# FilamentBox.net
KiCad netlist of a schematic drawn in EAGLE
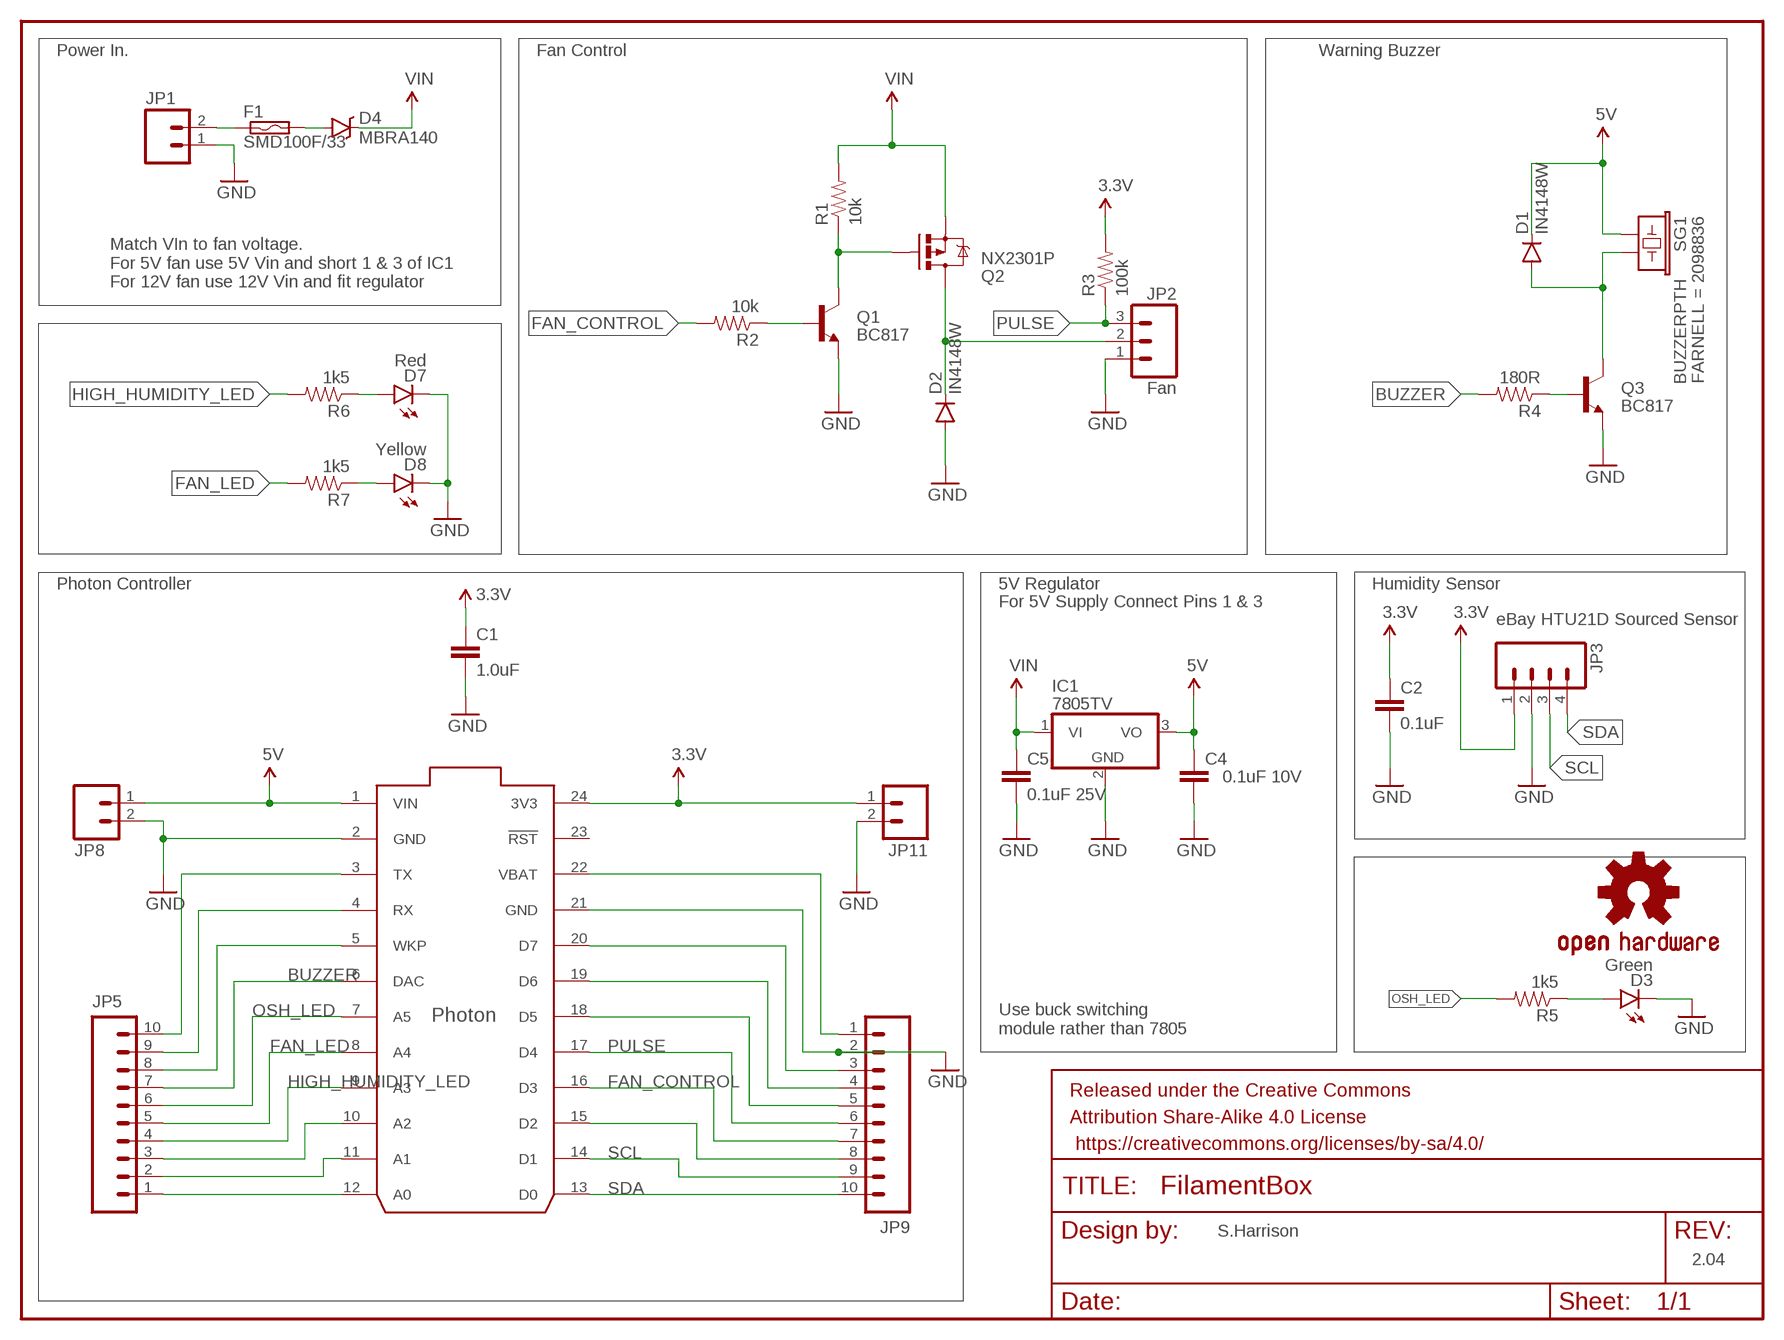
[diagram p0: schematic, sheet 1]

(export (version "E")
  (design (tool "Eeschema 10.0.6"))
  (components
    (comp (ref "C1")
      (value "1.0uF")
      (footprint "eagle-import:0805-CAP")
      (libsource (lib "eagle-import") (part "1.0UF-25V-+80/-20(0805){dblquote}"))
    )
    (comp (ref "C2")
      (value "0.1uF")
      (footprint "eagle-import:0805-CAP")
      (libsource (lib "eagle-import") (part "1.0UF-25V-+80/-20(0805){dblquote}"))
    )
    (comp (ref "C4")
      (value "0.1uF 10V")
      (footprint "eagle-import:0805-CAP")
      (libsource (lib "eagle-import") (part "1UF-25V-10%(0805){dblquote}"))
    )
    (comp (ref "C5")
      (value "0.1uF 25V")
      (footprint "eagle-import:0805-CAP")
      (libsource (lib "eagle-import") (part "1UF-25V-10%(0805){dblquote}"))
    )
    (comp (ref "D1")
      (value "IN4148W")
      (footprint "eagle-import:SOD-123")
      (libsource (lib "eagle-import") (part "DIODESOD123"))
    )
    (comp (ref "D2")
      (value "IN4148W")
      (footprint "eagle-import:SOD-123")
      (libsource (lib "eagle-import") (part "DIODESOD123"))
    )
    (comp (ref "D3")
      (value "Green")
      (footprint "eagle-import:LED-1206-BOTTOM")
      (libsource (lib "eagle-import") (part "LED1206-BOTTOM"))
    )
    (comp (ref "D4")
      (value "MBRA140")
      (footprint "eagle-import:SMA-DIODE")
      (libsource (lib "eagle-import") (part "DIODE-SCHOTTKY-MBRA140"))
    )
    (comp (ref "D7")
      (value "Red")
      (footprint "eagle-import:LED-1206-BOTTOM")
      (libsource (lib "eagle-import") (part "LED1206-BOTTOM"))
    )
    (comp (ref "D8")
      (value "Yellow")
      (footprint "eagle-import:LED-1206-BOTTOM")
      (libsource (lib "eagle-import") (part "LED1206-BOTTOM"))
    )
    (comp (ref "F1")
      (value "SMD100F/33")
      (footprint "eagle-import:SMD050F")
      (fields (field (name "MFG") "LITTLEFUSE") (field (name "MFGPART") "2920L075DR"))
      (libsource (lib "eagle-import") (part "SMDF/33100"))
    )
    (comp (ref "FRAME1")
      (value "FRAME-LETTER")
      (footprint "eagle-import:CREATIVE_COMMONS")
      (libsource (lib "eagle-import") (part "FRAME-LETTER"))
    )
    (comp (ref "IC1")
      (value "7805TV")
      (footprint "eagle-import:TO220V")
      (libsource (lib "eagle-import") (part "78TV05"))
    )
    (comp (ref "JP1")
      (value "M02POLAR")
      (footprint "eagle-import:MOLEX-1X2")
      (libsource (lib "eagle-import") (part "M02POLAR"))
    )
    (comp (ref "JP2")
      (value "Fan")
      (footprint "eagle-import:MOLEX-1X3")
      (libsource (lib "eagle-import") (part "M03POLAR"))
    )
    (comp (ref "JP3")
      (value "M04PTH")
      (footprint "eagle-import:1X04")
      (libsource (lib "eagle-import") (part "M04PTH"))
    )
    (comp (ref "JP5")
      (value "M10NO_SILK_PTH_FEMALE")
      (footprint "eagle-import:1X10_NO_SILK")
      (libsource (lib "eagle-import") (part "M10NO_SILK_PTH_FEMALE"))
    )
    (comp (ref "JP8")
      (value "M021X02_NO_SILK")
      (footprint "eagle-import:1X02_NO_SILK")
      (libsource (lib "eagle-import") (part "M021X02_NO_SILK"))
    )
    (comp (ref "JP9")
      (value "M10NO_SILK_PTH_FEMALE")
      (footprint "eagle-import:1X10_NO_SILK")
      (libsource (lib "eagle-import") (part "M10NO_SILK_PTH_FEMALE"))
    )
    (comp (ref "JP11")
      (value "M021X02_NO_SILK")
      (footprint "eagle-import:1X02_NO_SILK")
      (libsource (lib "eagle-import") (part "M021X02_NO_SILK"))
    )
    (comp (ref "LOGO1")
      (value "OSHW-LOGOL")
      (footprint "eagle-import:OSHW-LOGO-L")
      (libsource (lib "eagle-import") (part "OSHW-LOGOL"))
    )
    (comp (ref "Q1")
      (value "BC817")
      (footprint "eagle-import:SOT23-BEC")
      (libsource (lib "eagle-import") (part "BC817SMD-40"))
    )
    (comp (ref "Q2")
      (value "NX2301P")
      (footprint "eagle-import:SOT23-3")
      (libsource (lib "eagle-import") (part "MOSFET-PCHANNEL"))
    )
    (comp (ref "Q3")
      (value "BC817")
      (footprint "eagle-import:SOT23-BEC")
      (libsource (lib "eagle-import") (part "BC817SMD-40"))
    )
    (comp (ref "R1")
      (value "10k")
      (footprint "eagle-import:0805")
      (libsource (lib "eagle-import") (part "RESISTOR0805-RES"))
    )
    (comp (ref "R2")
      (value "10k")
      (footprint "eagle-import:0805")
      (libsource (lib "eagle-import") (part "RESISTOR0805-RES"))
    )
    (comp (ref "R3")
      (value "100k")
      (footprint "eagle-import:0805")
      (libsource (lib "eagle-import") (part "RESISTOR0805-RES"))
    )
    (comp (ref "R4")
      (value "180R")
      (footprint "eagle-import:0805")
      (libsource (lib "eagle-import") (part "RESISTOR0805-RES"))
    )
    (comp (ref "R5")
      (value "1k5")
      (footprint "eagle-import:0805")
      (libsource (lib "eagle-import") (part "RESISTOR0805-RES"))
    )
    (comp (ref "R6")
      (value "1k5")
      (footprint "eagle-import:0805")
      (libsource (lib "eagle-import") (part "RESISTOR0805-RES"))
    )
    (comp (ref "R7")
      (value "1k5")
      (footprint "eagle-import:0805")
      (libsource (lib "eagle-import") (part "RESISTOR0805-RES"))
    )
    (comp (ref "SG1")
      (value "BUZZERPTH")
      (footprint "eagle-import:BUZZER-12MM")
      (fields (field (name "FARNELL") "2098836"))
      (libsource (lib "eagle-import") (part "BUZZERPTH"))
    )
    (comp (ref "U3")
      (value "PHOTON")
      (footprint "eagle-import:PHOTON")
      (libsource (lib "eagle-import") (part "PHOTON_WITH_HEADERS"))
    )
  )
  (nets
    (net (code "1") (name "3.3V") (class "Default")
      (node (ref "C1") (pin "1") (pinfunction "1_1") (pintype "passive"))
      (node (ref "C2") (pin "1") (pinfunction "1_1") (pintype "passive"))
      (node (ref "JP11") (pin "1") (pinfunction "1_1") (pintype "passive"))
      (node (ref "JP3") (pin "1") (pinfunction "1_1") (pintype "passive"))
      (node (ref "R3") (pin "2") (pinfunction "2_2") (pintype "passive"))
      (node (ref "U3") (pin "24") (pinfunction "3V3_24") (pintype "power_in"))
    )
    (net (code "2") (name "5V") (class "Default")
      (node (ref "C4") (pin "1") (pinfunction "1_1") (pintype "passive"))
      (node (ref "D1") (pin "C") (pinfunction "C_C") (pintype "passive"))
      (node (ref "IC1") (pin "3") (pinfunction "VO_3") (pintype "passive"))
      (node (ref "JP8") (pin "1") (pinfunction "1_1") (pintype "passive"))
      (node (ref "SG1") (pin "+") (pinfunction "1_+") (pintype "passive"))
      (node (ref "U3") (pin "1") (pinfunction "VIN_1") (pintype "power_in"))
    )
    (net (code "3") (name "BUZZER") (class "Default")
      (node (ref "JP5") (pin "7") (pinfunction "7_7") (pintype "passive"))
      (node (ref "R4") (pin "2") (pinfunction "2_2") (pintype "passive"))
      (node (ref "U3") (pin "6") (pinfunction "DAC_6") (pintype "bidirectional"))
    )
    (net (code "4") (name "FAN_CONTROL") (class "Default")
      (node (ref "JP9") (pin "7") (pinfunction "7_7") (pintype "passive"))
      (node (ref "R2") (pin "2") (pinfunction "2_2") (pintype "passive"))
      (node (ref "U3") (pin "16") (pinfunction "D3_16") (pintype "bidirectional"))
    )
    (net (code "5") (name "FAN_LED") (class "Default")
      (node (ref "JP5") (pin "5") (pinfunction "5_5") (pintype "passive"))
      (node (ref "R7") (pin "2") (pinfunction "2_2") (pintype "passive"))
      (node (ref "U3") (pin "8") (pinfunction "A4_8") (pintype "bidirectional"))
    )
    (net (code "6") (name "GND") (class "Default")
      (node (ref "C1") (pin "2") (pinfunction "2_2") (pintype "passive"))
      (node (ref "C2") (pin "2") (pinfunction "2_2") (pintype "passive"))
      (node (ref "C4") (pin "2") (pinfunction "2_2") (pintype "passive"))
      (node (ref "C5") (pin "2") (pinfunction "2_2") (pintype "passive"))
      (node (ref "D2") (pin "A") (pinfunction "A_A") (pintype "passive"))
      (node (ref "D3") (pin "C") (pinfunction "C_C") (pintype "passive"))
      (node (ref "D7") (pin "C") (pinfunction "C_C") (pintype "passive"))
      (node (ref "D8") (pin "C") (pinfunction "C_C") (pintype "passive"))
      (node (ref "IC1") (pin "2") (pinfunction "GND_2") (pintype "passive"))
      (node (ref "JP1") (pin "1") (pinfunction "1_1") (pintype "passive"))
      (node (ref "JP11") (pin "2") (pinfunction "2_2") (pintype "passive"))
      (node (ref "JP2") (pin "1") (pinfunction "1_1") (pintype "passive"))
      (node (ref "JP3") (pin "2") (pinfunction "2_2") (pintype "passive"))
      (node (ref "JP8") (pin "2") (pinfunction "2_2") (pintype "passive"))
      (node (ref "JP9") (pin "2") (pinfunction "2_2") (pintype "passive"))
      (node (ref "Q1") (pin "E") (pinfunction "E_E") (pintype "passive"))
      (node (ref "Q3") (pin "E") (pinfunction "E_E") (pintype "passive"))
      (node (ref "U3") (pin "2") (pinfunction "GND_2") (pintype "power_in"))
      (node (ref "U3") (pin "21") (pinfunction "GND_21") (pintype "power_in"))
    )
    (net (code "7") (name "HIGH_HUMIDITY_LED") (class "Default")
      (node (ref "JP5") (pin "4") (pinfunction "4_4") (pintype "passive"))
      (node (ref "R6") (pin "2") (pinfunction "2_2") (pintype "passive"))
      (node (ref "U3") (pin "9") (pinfunction "A3_9") (pintype "bidirectional"))
    )
    (net (code "8") (name "Net-(D3-PadA)") (class "Default")
      (node (ref "D3") (pin "A") (pinfunction "A_A") (pintype "passive"))
      (node (ref "R5") (pin "1") (pinfunction "1_1") (pintype "passive"))
    )
    (net (code "9") (name "Net-(D4-PadA)") (class "Default")
      (node (ref "D4") (pin "A") (pinfunction "A_A") (pintype "passive"))
      (node (ref "F1") (pin "2") (pinfunction "2_2") (pintype "passive"))
    )
    (net (code "10") (name "Net-(D7-PadA)") (class "Default")
      (node (ref "D7") (pin "A") (pinfunction "A_A") (pintype "passive"))
      (node (ref "R6") (pin "1") (pinfunction "1_1") (pintype "passive"))
    )
    (net (code "11") (name "Net-(D8-PadA)") (class "Default")
      (node (ref "D8") (pin "A") (pinfunction "A_A") (pintype "passive"))
      (node (ref "R7") (pin "1") (pinfunction "1_1") (pintype "passive"))
    )
    (net (code "12") (name "Net-(F1-Pad1)") (class "Default")
      (node (ref "F1") (pin "1") (pinfunction "1_1") (pintype "passive"))
      (node (ref "JP1") (pin "2") (pinfunction "2_2") (pintype "passive"))
    )
    (net (code "13") (name "Net-(Q1-PadB)") (class "Default")
      (node (ref "Q1") (pin "B") (pinfunction "B_B") (pintype "passive"))
      (node (ref "R2") (pin "1") (pinfunction "1_1") (pintype "passive"))
    )
    (net (code "14") (name "Net-(Q2-D)") (class "Default")
      (node (ref "D2") (pin "C") (pinfunction "C_C") (pintype "passive"))
      (node (ref "JP2") (pin "2") (pinfunction "2_2") (pintype "passive"))
      (node (ref "Q2") (pin "3") (pinfunction "D_3") (pintype "passive"))
    )
    (net (code "15") (name "Net-(Q2-G)") (class "Default")
      (node (ref "Q1") (pin "C") (pinfunction "C_C") (pintype "passive"))
      (node (ref "Q2") (pin "1") (pinfunction "G_1") (pintype "passive"))
      (node (ref "R1") (pin "1") (pinfunction "1_1") (pintype "passive"))
    )
    (net (code "16") (name "Net-(Q3-PadB)") (class "Default")
      (node (ref "Q3") (pin "B") (pinfunction "B_B") (pintype "passive"))
      (node (ref "R4") (pin "1") (pinfunction "1_1") (pintype "passive"))
    )
    (net (code "17") (name "Net-(SG1-2)") (class "Default")
      (node (ref "D1") (pin "A") (pinfunction "A_A") (pintype "passive"))
      (node (ref "Q3") (pin "C") (pinfunction "C_C") (pintype "passive"))
      (node (ref "SG1") (pin "-") (pinfunction "2_-") (pintype "passive"))
    )
    (net (code "18") (name "Net-(U3-A0)") (class "Default")
      (node (ref "JP5") (pin "1") (pinfunction "1_1") (pintype "passive"))
      (node (ref "U3") (pin "12") (pinfunction "A0_12") (pintype "bidirectional"))
    )
    (net (code "19") (name "Net-(U3-A1)") (class "Default")
      (node (ref "JP5") (pin "2") (pinfunction "2_2") (pintype "passive"))
      (node (ref "U3") (pin "11") (pinfunction "A1_11") (pintype "bidirectional"))
    )
    (net (code "20") (name "Net-(U3-A2)") (class "Default")
      (node (ref "JP5") (pin "3") (pinfunction "3_3") (pintype "passive"))
      (node (ref "U3") (pin "10") (pinfunction "A2_10") (pintype "bidirectional"))
    )
    (net (code "21") (name "Net-(U3-D2)") (class "Default")
      (node (ref "JP9") (pin "8") (pinfunction "8_8") (pintype "passive"))
      (node (ref "U3") (pin "15") (pinfunction "D2_15") (pintype "bidirectional"))
    )
    (net (code "22") (name "Net-(U3-D5)") (class "Default")
      (node (ref "JP9") (pin "5") (pinfunction "5_5") (pintype "passive"))
      (node (ref "U3") (pin "18") (pinfunction "D5_18") (pintype "bidirectional"))
    )
    (net (code "23") (name "Net-(U3-D6)") (class "Default")
      (node (ref "JP9") (pin "4") (pinfunction "4_4") (pintype "passive"))
      (node (ref "U3") (pin "19") (pinfunction "D6_19") (pintype "bidirectional"))
    )
    (net (code "24") (name "Net-(U3-D7)") (class "Default")
      (node (ref "JP9") (pin "3") (pinfunction "3_3") (pintype "passive"))
      (node (ref "U3") (pin "20") (pinfunction "D7_20") (pintype "bidirectional"))
    )
    (net (code "25") (name "Net-(U3-RX)") (class "Default")
      (node (ref "JP5") (pin "9") (pinfunction "9_9") (pintype "passive"))
      (node (ref "U3") (pin "4") (pinfunction "RX_4") (pintype "bidirectional"))
    )
    (net (code "26") (name "Net-(U3-TX)") (class "Default")
      (node (ref "JP5") (pin "10") (pinfunction "10_10") (pintype "passive"))
      (node (ref "U3") (pin "3") (pinfunction "TX_3") (pintype "bidirectional"))
    )
    (net (code "27") (name "Net-(U3-VBAT)") (class "Default")
      (node (ref "JP9") (pin "1") (pinfunction "1_1") (pintype "passive"))
      (node (ref "U3") (pin "22") (pinfunction "VBAT_22") (pintype "power_in"))
    )
    (net (code "28") (name "Net-(U3-WKP)") (class "Default")
      (node (ref "JP5") (pin "8") (pinfunction "8_8") (pintype "passive"))
      (node (ref "U3") (pin "5") (pinfunction "WKP_5") (pintype "bidirectional"))
    )
    (net (code "29") (name "OSH_LED") (class "Default")
      (node (ref "JP5") (pin "6") (pinfunction "6_6") (pintype "passive"))
      (node (ref "R5") (pin "2") (pinfunction "2_2") (pintype "passive"))
      (node (ref "U3") (pin "7") (pinfunction "A5_7") (pintype "bidirectional"))
    )
    (net (code "30") (name "PULSE") (class "Default")
      (node (ref "JP2") (pin "3") (pinfunction "3_3") (pintype "passive"))
      (node (ref "JP9") (pin "6") (pinfunction "6_6") (pintype "passive"))
      (node (ref "R3") (pin "1") (pinfunction "1_1") (pintype "passive"))
      (node (ref "U3") (pin "17") (pinfunction "D4_17") (pintype "bidirectional"))
    )
    (net (code "31") (name "SCL") (class "Default")
      (node (ref "JP3") (pin "3") (pinfunction "3_3") (pintype "passive"))
      (node (ref "JP9") (pin "9") (pinfunction "9_9") (pintype "passive"))
      (node (ref "U3") (pin "14") (pinfunction "D1_14") (pintype "bidirectional"))
    )
    (net (code "32") (name "SDA") (class "Default")
      (node (ref "JP3") (pin "4") (pinfunction "4_4") (pintype "passive"))
      (node (ref "JP9") (pin "10") (pinfunction "10_10") (pintype "passive"))
      (node (ref "U3") (pin "13") (pinfunction "D0_13") (pintype "bidirectional"))
    )
    (net (code "33") (name "VIN") (class "Default")
      (node (ref "C5") (pin "1") (pinfunction "1_1") (pintype "passive"))
      (node (ref "D4") (pin "C") (pinfunction "C_C") (pintype "passive"))
      (node (ref "IC1") (pin "1") (pinfunction "VI_1") (pintype "input"))
      (node (ref "Q2") (pin "2") (pinfunction "S_2") (pintype "passive"))
      (node (ref "R1") (pin "2") (pinfunction "2_2") (pintype "passive"))
    )
    (net (code "34") (name "unconnected-(U3-~{RST}-Pad23)") (class "Default")
      (node (ref "U3") (pin "23") (pinfunction "~{RST}_23") (pintype "bidirectional"))
    )
  )
)
